# power-reset_board_v0_2.net
KiCad netlist of a schematic drawn in EAGLE
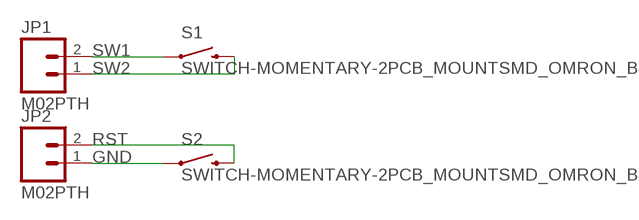
[diagram p0: schematic, sheet 1]

(export (version "E")
  (design (tool "Eeschema 10.0.6"))
  (components
    (comp (ref "JP1")
      (value "M02PTH")
      (footprint "eagle-import:1X02")
      (libsource (lib "eagle-import") (part "M02PTH"))
    )
    (comp (ref "JP2")
      (value "M02PTH")
      (footprint "eagle-import:1X02")
      (libsource (lib "eagle-import") (part "M02PTH"))
    )
    (comp (ref "S1")
      (value "SWITCH-MOMENTARY-2PCB_MOUNTSMD_OMRON_B3S_100X")
      (footprint "eagle-import:TACTILE_SWITCH_LARGE")
      (libsource (lib "eagle-import") (part "SWITCH-MOMENTARY-2SMD_OMRON_B3S_100XPCB_MOUNT"))
    )
    (comp (ref "S2")
      (value "SWITCH-MOMENTARY-2PCB_MOUNTSMD_OMRON_B3S_100X")
      (footprint "eagle-import:TACTILE_SWITCH_LARGE")
      (libsource (lib "eagle-import") (part "SWITCH-MOMENTARY-2SMD_OMRON_B3S_100XPCB_MOUNT"))
    )
  )
  (nets
    (net (code "1") (name "/GND") (class "Default")
      (node (ref "JP2") (pin "1") (pinfunction "1_1") (pintype "passive"))
      (node (ref "S2") (pin "1") (pinfunction "1_1") (pintype "passive"))
    )
    (net (code "2") (name "/RST") (class "Default")
      (node (ref "JP2") (pin "2") (pinfunction "2_2") (pintype "passive"))
      (node (ref "S2") (pin "3") (pinfunction "2_3") (pintype "passive"))
    )
    (net (code "3") (name "/SW1") (class "Default")
      (node (ref "JP1") (pin "2") (pinfunction "2_2") (pintype "passive"))
      (node (ref "S1") (pin "1") (pinfunction "1_1") (pintype "passive"))
    )
    (net (code "4") (name "/SW2") (class "Default")
      (node (ref "JP1") (pin "1") (pinfunction "1_1") (pintype "passive"))
      (node (ref "S1") (pin "3") (pinfunction "2_3") (pintype "passive"))
    )
  )
)
